# drucksensor.net
KiCad netlist of a schematic drawn in EAGLE
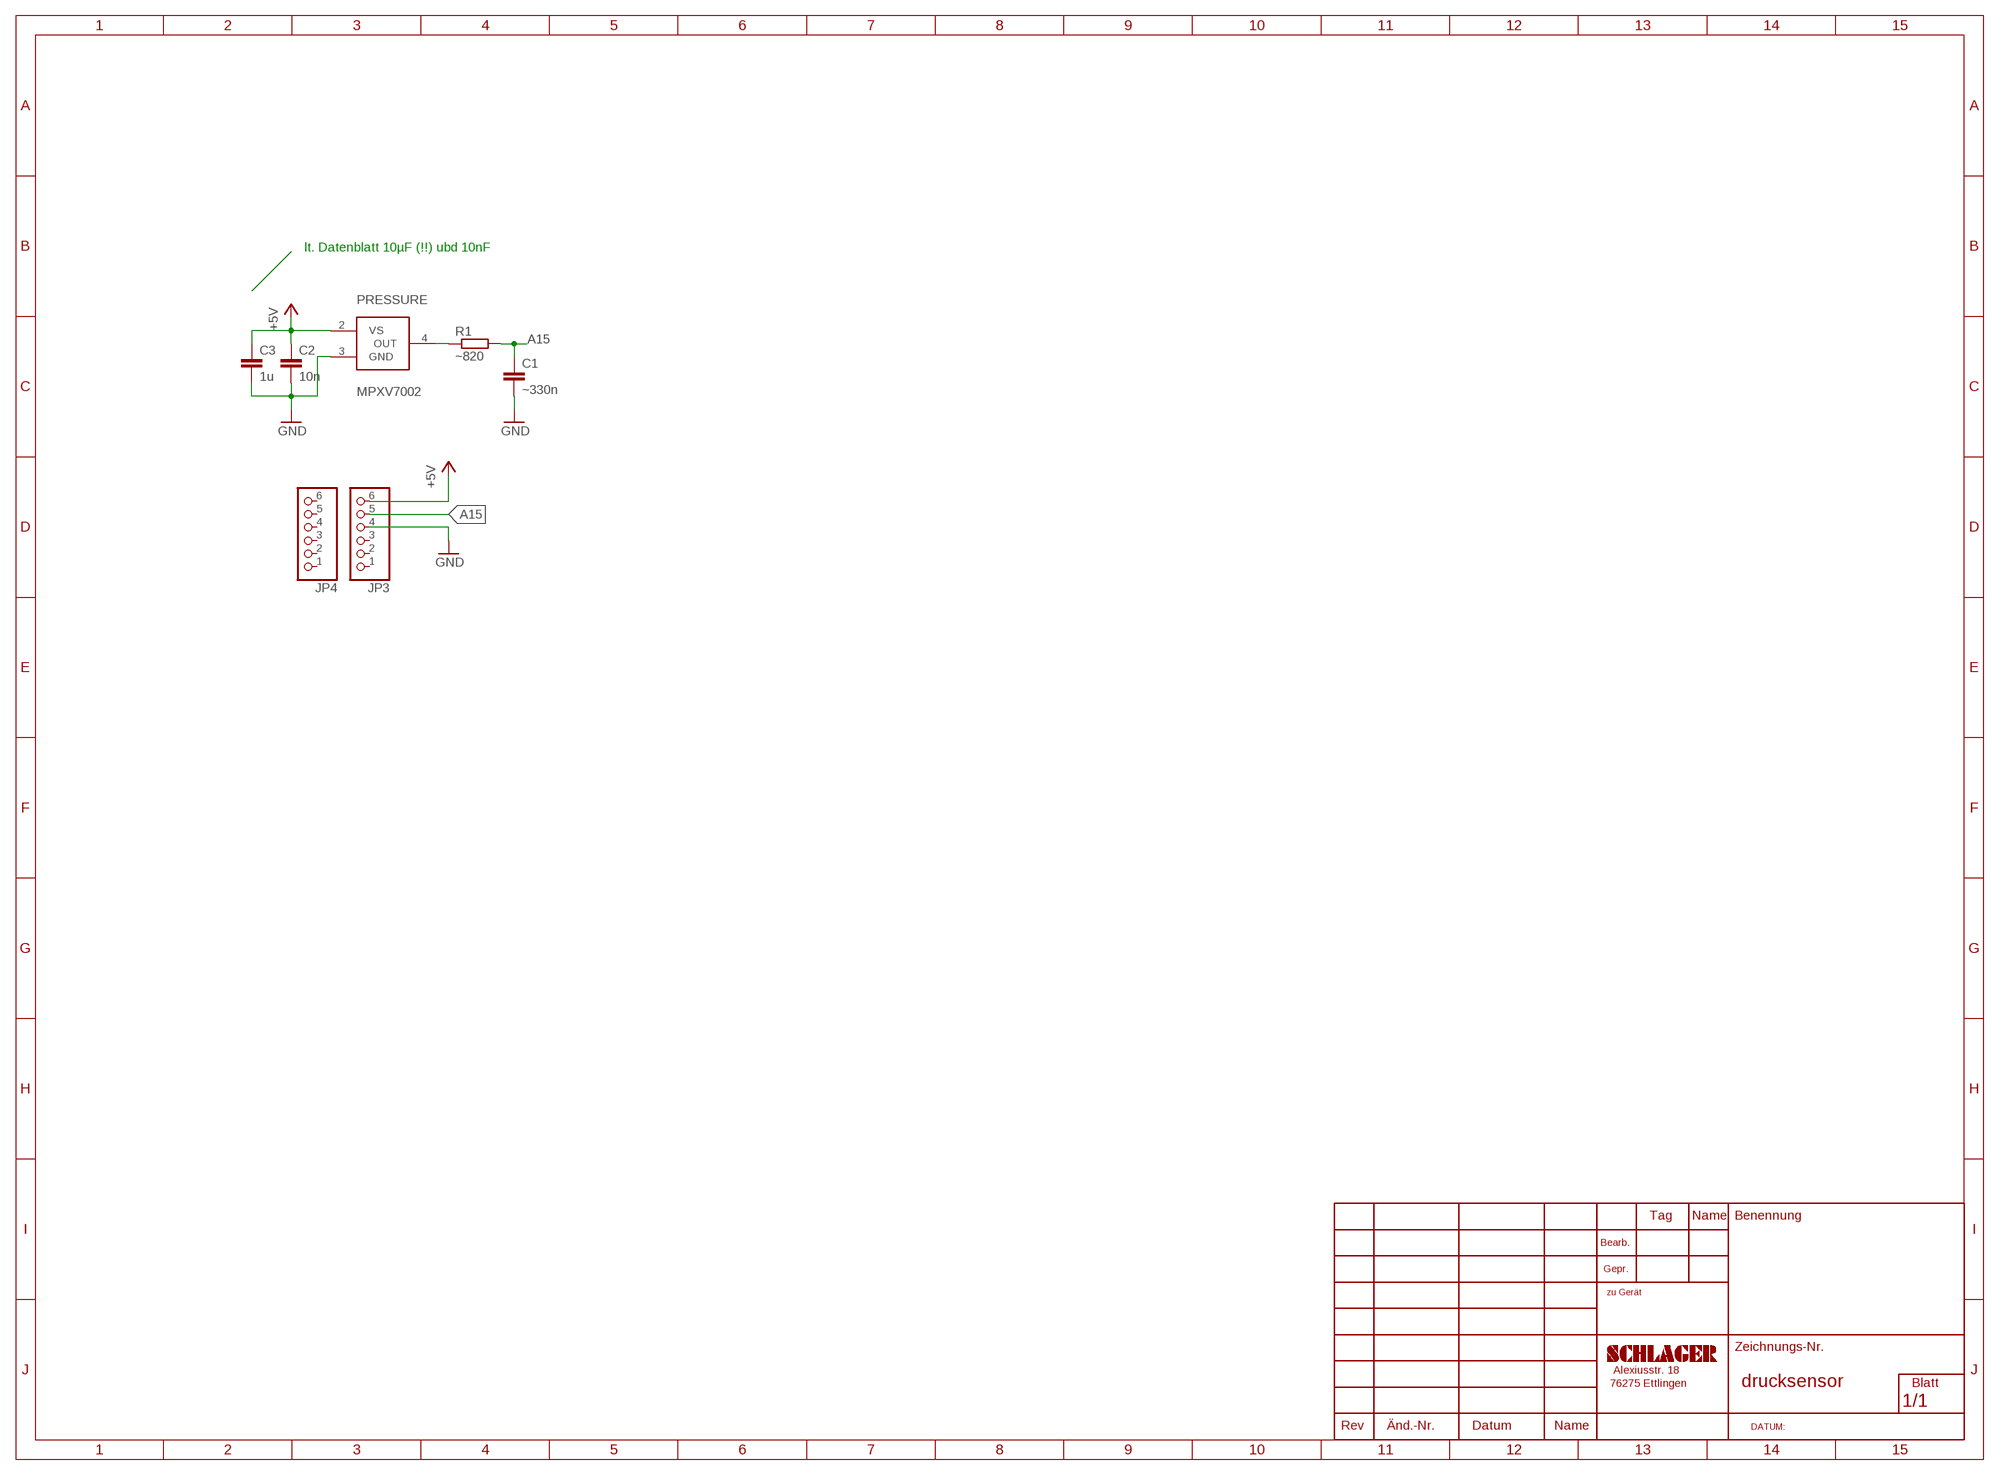
[diagram p0: schematic, sheet 1]

(export (version "E")
  (design (tool "Eeschema 10.0.6"))
  (components
    (comp (ref "C1")
      (value "~330n")
      (footprint "eagle-import:C0805")
      (libsource (lib "eagle-import") (part "C-EUC0805"))
    )
    (comp (ref "C2")
      (value "10n")
      (footprint "eagle-import:C0805")
      (libsource (lib "eagle-import") (part "C-EUC0805"))
    )
    (comp (ref "C3")
      (value "1u")
      (footprint "eagle-import:C0805")
      (libsource (lib "eagle-import") (part "C-EUC0805"))
    )
    (comp (ref "JP3")
      (value "PINHD-1X6")
      (footprint "eagle-import:1X06")
      (libsource (lib "eagle-import") (part "PINHD-1X6"))
    )
    (comp (ref "JP4")
      (value "PINHD-1X6")
      (footprint "eagle-import:1X06")
      (libsource (lib "eagle-import") (part "PINHD-1X6"))
    )
    (comp (ref "PRESSURE")
      (value "MPXV7002")
      (footprint "eagle-import:MPXV7002DP")
      (libsource (lib "eagle-import") (part "MPXV7002"))
    )
    (comp (ref "R1")
      (value "~820")
      (footprint "eagle-import:R0805")
      (libsource (lib "eagle-import") (part "R-EU_R0805"))
    )
  )
  (nets
    (net (code "1") (name "+5V") (class "Default")
      (node (ref "C2") (pin "1") (pinfunction "1_1") (pintype "passive"))
      (node (ref "C3") (pin "1") (pinfunction "1_1") (pintype "passive"))
      (node (ref "JP3") (pin "6") (pinfunction "6_6") (pintype "passive"))
      (node (ref "PRESSURE") (pin "2") (pinfunction "VS_2") (pintype "bidirectional"))
    )
    (net (code "2") (name "A15") (class "Default")
      (node (ref "C1") (pin "1") (pinfunction "1_1") (pintype "passive"))
      (node (ref "JP3") (pin "5") (pinfunction "5_5") (pintype "passive"))
      (node (ref "R1") (pin "2") (pinfunction "2_2") (pintype "passive"))
    )
    (net (code "3") (name "GND") (class "Default")
      (node (ref "C1") (pin "2") (pinfunction "2_2") (pintype "passive"))
      (node (ref "C2") (pin "2") (pinfunction "2_2") (pintype "passive"))
      (node (ref "C3") (pin "2") (pinfunction "2_2") (pintype "passive"))
      (node (ref "JP3") (pin "4") (pinfunction "4_4") (pintype "passive"))
      (node (ref "PRESSURE") (pin "3") (pinfunction "GND_3") (pintype "bidirectional"))
    )
    (net (code "4") (name "Net-(PRESSURE-OUT)") (class "Default")
      (node (ref "PRESSURE") (pin "4") (pinfunction "OUT_4") (pintype "bidirectional"))
      (node (ref "R1") (pin "1") (pinfunction "1_1") (pintype "passive"))
    )
    (net (code "5") (name "unconnected-(JP3-Pad1)") (class "Default")
      (node (ref "JP3") (pin "1") (pinfunction "1_1") (pintype "passive"))
    )
    (net (code "6") (name "unconnected-(JP3-Pad2)") (class "Default")
      (node (ref "JP3") (pin "2") (pinfunction "2_2") (pintype "passive"))
    )
    (net (code "7") (name "unconnected-(JP3-Pad3)") (class "Default")
      (node (ref "JP3") (pin "3") (pinfunction "3_3") (pintype "passive"))
    )
    (net (code "8") (name "unconnected-(JP4-Pad1)") (class "Default")
      (node (ref "JP4") (pin "1") (pinfunction "1_1") (pintype "passive"))
    )
    (net (code "9") (name "unconnected-(JP4-Pad2)") (class "Default")
      (node (ref "JP4") (pin "2") (pinfunction "2_2") (pintype "passive"))
    )
    (net (code "10") (name "unconnected-(JP4-Pad3)") (class "Default")
      (node (ref "JP4") (pin "3") (pinfunction "3_3") (pintype "passive"))
    )
    (net (code "11") (name "unconnected-(JP4-Pad4)") (class "Default")
      (node (ref "JP4") (pin "4") (pinfunction "4_4") (pintype "passive"))
    )
    (net (code "12") (name "unconnected-(JP4-Pad5)") (class "Default")
      (node (ref "JP4") (pin "5") (pinfunction "5_5") (pintype "passive"))
    )
    (net (code "13") (name "unconnected-(JP4-Pad6)") (class "Default")
      (node (ref "JP4") (pin "6") (pinfunction "6_6") (pintype "passive"))
    )
  )
)
